# audio.net
KiCad netlist of a schematic drawn in Altium Designer
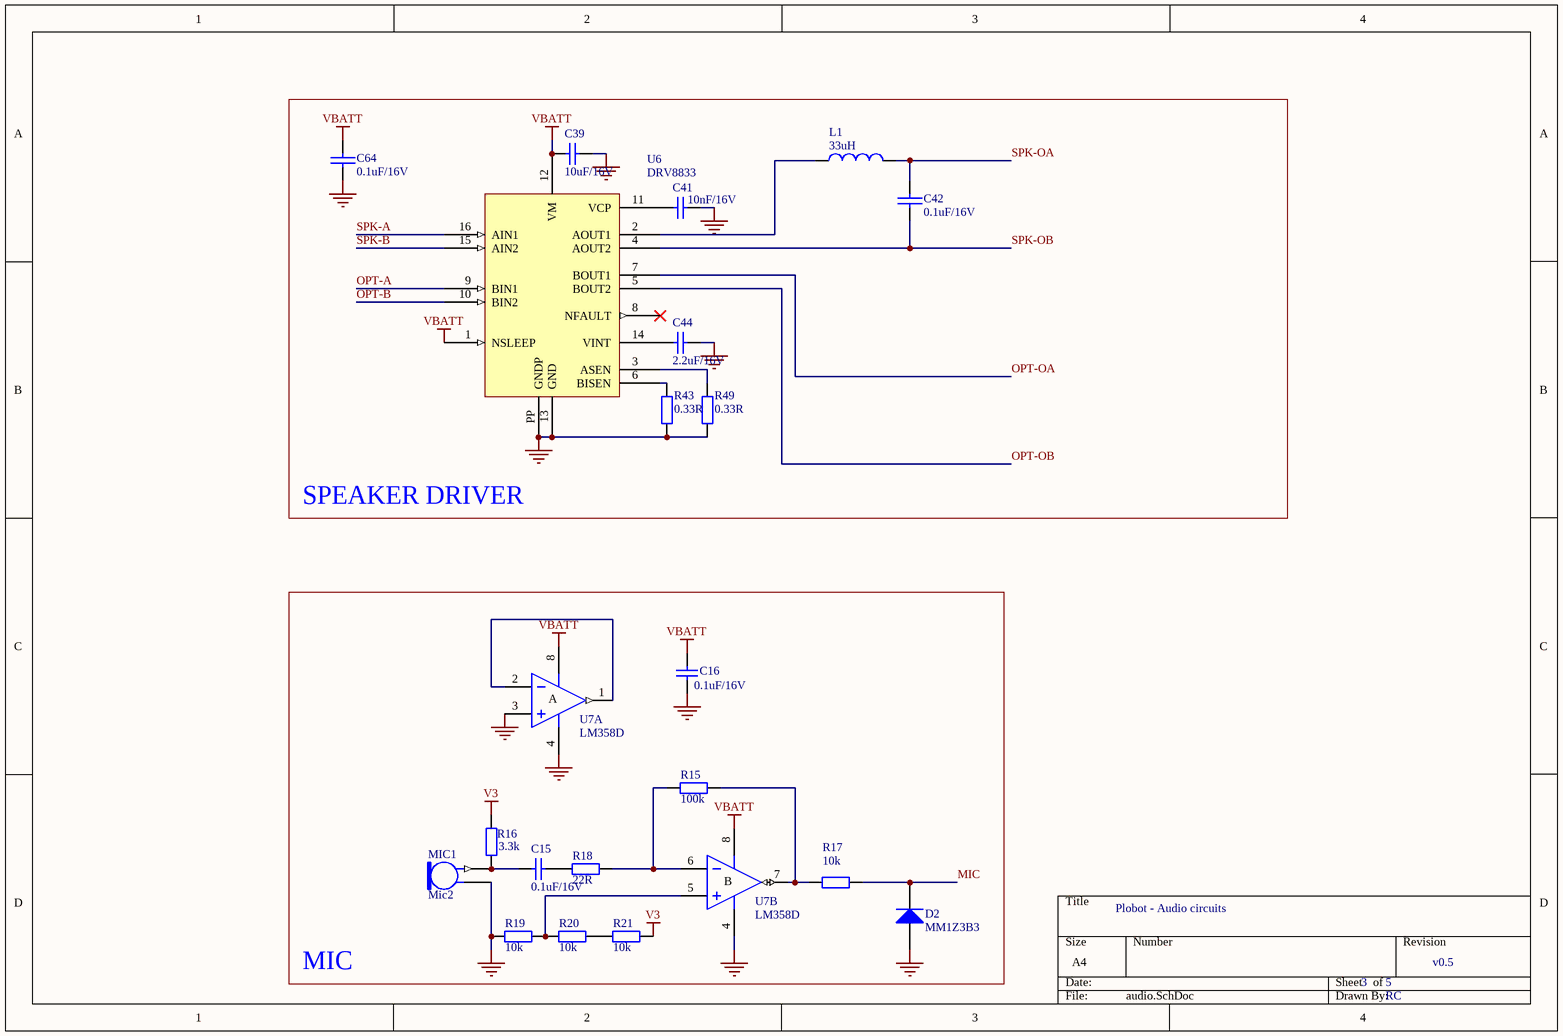
[diagram p0: audio.SchDoc]

(export (version "E")
  (design (tool "Eeschema 10.0.6"))
  (components
    (comp (ref "C15")
      (value "0.1uF/16V")
      (footprint "CAPC1608N")
      (description "Capacitor")
      (fields (field (name "PUBLISHER") "Altium Limited"))
      (libsource (lib "") (part "Cap_1"))
    )
    (comp (ref "C16")
      (value "0.1uF/16V")
      (footprint "CAPC1608N")
      (description "Capacitor")
      (fields (field (name "PUBLISHER") "Altium Limited"))
      (libsource (lib "*") (part "Cap"))
    )
    (comp (ref "C39")
      (value "10uF/16V")
      (footprint "CAPC1608N")
      (description "Capacitor")
      (fields (field (name "PUBLISHER") "Altium Limited"))
      (libsource (lib "main_pcb") (part "Cap_2"))
    )
    (comp (ref "C41")
      (value "10nF/16V")
      (footprint "CAPC1608N")
      (description "Capacitor")
      (fields (field (name "PUBLISHER") "Altium Limited"))
      (libsource (lib "*") (part "Cap"))
    )
    (comp (ref "C42")
      (value "0.1uF/16V")
      (footprint "CAPC1608N")
      (description "Capacitor")
      (libsource (lib "") (part "Cap_2"))
    )
    (comp (ref "C44")
      (value "2.2uF/16V")
      (footprint "CAPC1608N")
      (description "Capacitor")
      (fields (field (name "PUBLISHER") "Altium Limited"))
      (libsource (lib "*") (part "Cap"))
    )
    (comp (ref "C64")
      (value "0.1uF/16V")
      (footprint "CAPC1608N")
      (description "Capacitor")
      (libsource (lib "") (part "Cap_2"))
    )
    (comp (ref "D2")
      (value "MM1Z3B3")
      (footprint "SOD123/X.85")
      (description "Default Diode")
      (fields (field (name "PUBLISHER") "Altium Limited"))
      (libsource (lib "Miscellaneous Devices") (part "Diode"))
    )
    (comp (ref "L1")
      (value "33uH")
      (footprint "INDC1608N")
      (description "Inductor")
      (fields (field (name "PUBLISHER") "Altium Limited"))
      (libsource (lib "Miscellaneous Devices") (part "Inductor"))
    )
    (comp (ref "MIC1")
      (value "Mic2")
      (footprint "plobot_review:electret_6mm")
      (description "Microphone")
      (fields (field (name "PUBLISHER") "*"))
      (libsource (lib "*") (part "Mic2"))
    )
    (comp (ref "R15")
      (value "100k")
      (footprint "plobot_review:RESC1608N")
      (description "Resistor")
      (fields (field (name "PUBLISHER") "Altium Limited"))
      (libsource (lib "") (part "Res2_1"))
    )
    (comp (ref "R16")
      (value "3.3k")
      (footprint "plobot_review:RESC1608N")
      (description "Resistor")
      (fields (field (name "PUBLISHER") "Altium Limited"))
      (libsource (lib "") (part "Res2_2"))
    )
    (comp (ref "R17")
      (value "10k")
      (footprint "plobot_review:RESC1608N")
      (description "Resistor")
      (fields (field (name "PUBLISHER") "Altium Limited"))
      (libsource (lib "") (part "Res2_1"))
    )
    (comp (ref "R18")
      (value "22R")
      (footprint "plobot_review:RESC1608N")
      (description "Resistor")
      (fields (field (name "PUBLISHER") "Altium Limited"))
      (libsource (lib "") (part "Res2_1"))
    )
    (comp (ref "R19")
      (value "10k")
      (footprint "plobot_review:RESC1608N")
      (description "Resistor")
      (fields (field (name "PUBLISHER") "Altium Limited"))
      (libsource (lib "") (part "Res2_1"))
    )
    (comp (ref "R20")
      (value "10k")
      (footprint "plobot_review:RESC1608N")
      (description "Resistor")
      (fields (field (name "PUBLISHER") "Altium Limited"))
      (libsource (lib "") (part "Res2_1"))
    )
    (comp (ref "R21")
      (value "10k")
      (footprint "plobot_review:RESC1608N")
      (description "Resistor")
      (fields (field (name "PUBLISHER") "Altium Limited"))
      (libsource (lib "") (part "Res2_1"))
    )
    (comp (ref "R43")
      (value "0.33R")
      (footprint "RESC1608N")
      (description "Resistor")
      (fields (field (name "PUBLISHER") "Altium Limited"))
      (libsource (lib "*") (part "Res2"))
    )
    (comp (ref "R49")
      (value "0.33R")
      (footprint "RESC1608N")
      (description "Resistor")
      (fields (field (name "PUBLISHER") "Altium Limited"))
      (libsource (lib "*") (part "Res2"))
    )
    (comp (ref "U6")
      (value "DRV8833")
      (footprint "plobot_review:DRV8833")
      (libsource (lib "components") (part "DRV8833"))
    )
    (comp (ref "U7")
      (value "LM358D")
      (footprint "plobot_review:LM358D")
      (description "Dual Operational Amplifier")
      (fields (field (name "PUBLISHER") "Altium Limited"))
      (libsource (lib "TI Operational Amplifier") (part "LM358D"))
    )
  )
  (nets
    (net (code "1") (name "/MIC") (class "Default")
      (node (ref "D2") (pin "1") (pinfunction "K_1") (pintype "passive"))
      (node (ref "R17") (pin "2") (pinfunction "2_2") (pintype "passive"))
    )
    (net (code "2") (name "/OPT-A") (class "Default")
      (node (ref "U6") (pin "9") (pinfunction "BIN1_9") (pintype "input"))
    )
    (net (code "3") (name "/OPT-B") (class "Default")
      (node (ref "U6") (pin "10") (pinfunction "BIN2_10") (pintype "input"))
    )
    (net (code "4") (name "/OPT-OA") (class "Default")
      (node (ref "U6") (pin "7") (pinfunction "BOUT1_7") (pintype "power_in"))
    )
    (net (code "5") (name "/OPT-OB") (class "Default")
      (node (ref "U6") (pin "5") (pinfunction "BOUT2_5") (pintype "power_in"))
    )
    (net (code "6") (name "/SPK-A") (class "Default")
      (node (ref "U6") (pin "16") (pinfunction "AIN1_16") (pintype "input"))
    )
    (net (code "7") (name "/SPK-B") (class "Default")
      (node (ref "U6") (pin "15") (pinfunction "AIN2_15") (pintype "input"))
    )
    (net (code "8") (name "/SPK-OA") (class "Default")
      (node (ref "C42") (pin "2") (pinfunction "2_2") (pintype "passive"))
      (node (ref "L1") (pin "2") (pinfunction "2_2") (pintype "passive"))
    )
    (net (code "9") (name "/SPK-OB") (class "Default")
      (node (ref "C42") (pin "1") (pinfunction "1_1") (pintype "passive"))
      (node (ref "U6") (pin "4") (pinfunction "AOUT2_4") (pintype "power_in"))
    )
    (net (code "10") (name "GND") (class "Default")
      (node (ref "C16") (pin "2") (pinfunction "2_2") (pintype "passive"))
      (node (ref "C39") (pin "1") (pinfunction "1_1") (pintype "passive"))
      (node (ref "C41") (pin "1") (pinfunction "1_1") (pintype "passive"))
      (node (ref "C44") (pin "1") (pinfunction "1_1") (pintype "passive"))
      (node (ref "C64") (pin "1") (pinfunction "1_1") (pintype "passive"))
      (node (ref "D2") (pin "2") (pinfunction "A_2") (pintype "passive"))
      (node (ref "MIC1") (pin "2") (pinfunction "2_2") (pintype "power_in"))
      (node (ref "R19") (pin "1") (pinfunction "1_1") (pintype "passive"))
      (node (ref "R43") (pin "1") (pinfunction "1_1") (pintype "passive"))
      (node (ref "R49") (pin "1") (pinfunction "1_1") (pintype "passive"))
      (node (ref "U6") (pin "13") (pinfunction "GND_13") (pintype "power_in"))
      (node (ref "U6") (pin "PP") (pinfunction "GNDP_PP") (pintype "power_in"))
      (node (ref "U7") (pin "3") (pinfunction "IN+_3") (pintype "passive"))
      (node (ref "U7") (pin "4") (pinfunction "V-_4") (pintype "power_in"))
    )
    (net (code "11") (name "Net-(C15-Pad1)") (class "Default")
      (node (ref "C15") (pin "1") (pinfunction "1_1") (pintype "passive"))
      (node (ref "R18") (pin "1") (pinfunction "1_1") (pintype "passive"))
    )
    (net (code "12") (name "Net-(C15-Pad2)") (class "Default")
      (node (ref "C15") (pin "2") (pinfunction "2_2") (pintype "passive"))
      (node (ref "MIC1") (pin "1") (pinfunction "1_1") (pintype "output"))
      (node (ref "R16") (pin "2") (pinfunction "2_2") (pintype "passive"))
    )
    (net (code "13") (name "Net-(R20-Pad2)") (class "Default")
      (node (ref "R20") (pin "2") (pinfunction "2_2") (pintype "passive"))
      (node (ref "R21") (pin "1") (pinfunction "1_1") (pintype "passive"))
    )
    (net (code "14") (name "Net-(U6-AOUT1)") (class "Default")
      (node (ref "L1") (pin "1") (pinfunction "1_1") (pintype "passive"))
      (node (ref "U6") (pin "2") (pinfunction "AOUT1_2") (pintype "power_in"))
    )
    (net (code "15") (name "Net-(U6-ASEN)") (class "Default")
      (node (ref "R49") (pin "2") (pinfunction "2_2") (pintype "passive"))
      (node (ref "U6") (pin "3") (pinfunction "ASEN_3") (pintype "power_in"))
    )
    (net (code "16") (name "Net-(U6-BISEN)") (class "Default")
      (node (ref "R43") (pin "2") (pinfunction "2_2") (pintype "passive"))
      (node (ref "U6") (pin "6") (pinfunction "BISEN_6") (pintype "power_in"))
    )
    (net (code "17") (name "Net-(U6-VCP)") (class "Default")
      (node (ref "C41") (pin "2") (pinfunction "2_2") (pintype "passive"))
      (node (ref "U6") (pin "11") (pinfunction "VCP_11") (pintype "power_in"))
    )
    (net (code "18") (name "Net-(U6-VINT)") (class "Default")
      (node (ref "C44") (pin "2") (pinfunction "2_2") (pintype "passive"))
      (node (ref "U6") (pin "14") (pinfunction "VINT_14") (pintype "power_in"))
    )
    (net (code "19") (name "Net-(U7A-IN-)") (class "Default")
      (node (ref "U7") (pin "1") (pinfunction "OUT_1") (pintype "output"))
      (node (ref "U7") (pin "2") (pinfunction "IN-_2") (pintype "passive"))
    )
    (net (code "20") (name "Net-(U7B-IN+)") (class "Default")
      (node (ref "R19") (pin "2") (pinfunction "2_2") (pintype "passive"))
      (node (ref "R20") (pin "1") (pinfunction "1_1") (pintype "passive"))
      (node (ref "U7") (pin "5") (pinfunction "IN+_5") (pintype "passive"))
    )
    (net (code "21") (name "Net-(U7B-IN-)") (class "Default")
      (node (ref "R15") (pin "1") (pinfunction "1_1") (pintype "passive"))
      (node (ref "R18") (pin "2") (pinfunction "2_2") (pintype "passive"))
      (node (ref "U7") (pin "6") (pinfunction "IN-_6") (pintype "passive"))
    )
    (net (code "22") (name "Net-(U7B-OUT)") (class "Default")
      (node (ref "R15") (pin "2") (pinfunction "2_2") (pintype "passive"))
      (node (ref "R17") (pin "1") (pinfunction "1_1") (pintype "passive"))
      (node (ref "U7") (pin "7") (pinfunction "OUT_7") (pintype "bidirectional"))
    )
    (net (code "23") (name "V3") (class "Default")
      (node (ref "R16") (pin "1") (pinfunction "1_1") (pintype "passive"))
      (node (ref "R21") (pin "2") (pinfunction "2_2") (pintype "passive"))
    )
    (net (code "24") (name "VBATT") (class "Default")
      (node (ref "C16") (pin "1") (pinfunction "1_1") (pintype "passive"))
      (node (ref "C39") (pin "2") (pinfunction "2_2") (pintype "passive"))
      (node (ref "C64") (pin "2") (pinfunction "2_2") (pintype "passive"))
      (node (ref "U6") (pin "1") (pinfunction "NSLEEP_1") (pintype "input"))
      (node (ref "U6") (pin "12") (pinfunction "VM_12") (pintype "power_in"))
      (node (ref "U7") (pin "8") (pinfunction "V+_8") (pintype "power_in"))
    )
    (net (code "25") (name "unconnected-(U6-NFAULT-Pad8)") (class "Default")
      (node (ref "U6") (pin "8") (pinfunction "NFAULT_8") (pintype "output+no_connect"))
    )
  )
)
